# EncoderPCB_V3.net
KiCad netlist of a schematic drawn in EAGLE
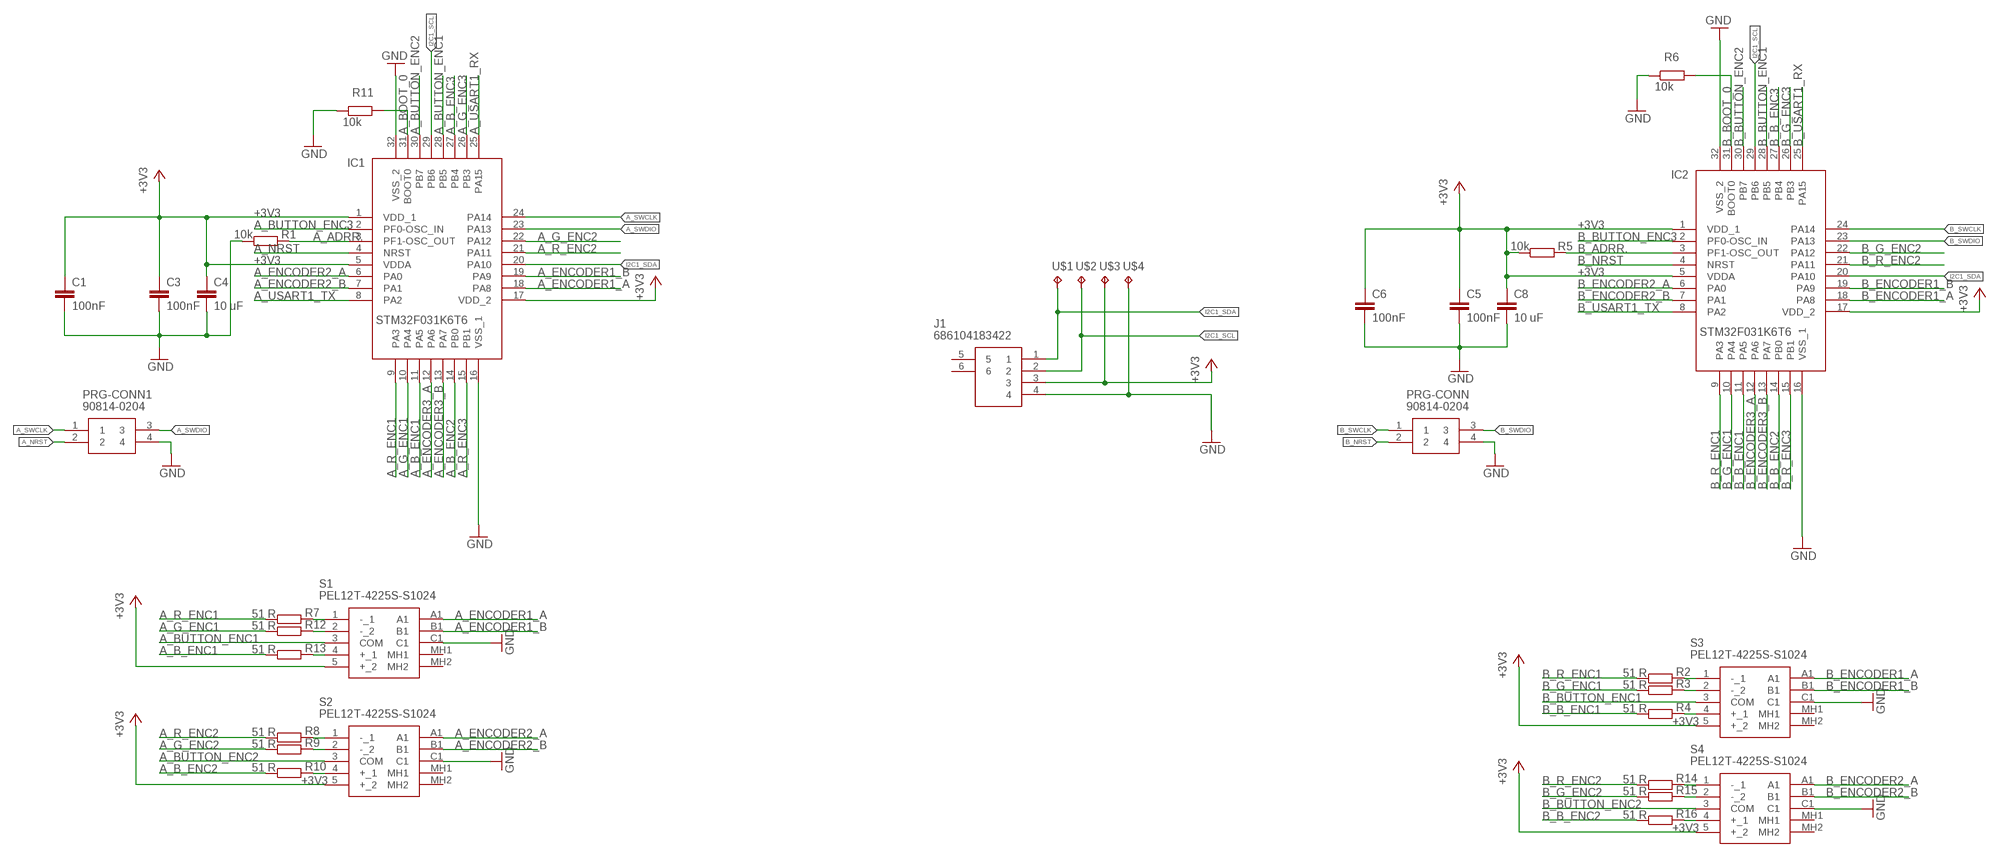
[diagram p0: schematic, sheet 1]

(export (version "E")
  (design (tool "Eeschema 10.0.6"))
  (components
    (comp (ref "C1")
      (value "100nF")
      (footprint "eagle-import:C0603")
      (libsource (lib "eagle-import") (part "CAPACITOR{dblquote}"))
    )
    (comp (ref "C3")
      (value "100nF")
      (footprint "eagle-import:C0603")
      (libsource (lib "eagle-import") (part "CAPACITOR{dblquote}"))
    )
    (comp (ref "C4")
      (value "10 uF")
      (footprint "eagle-import:C1206")
      (libsource (lib "eagle-import") (part "CAPACITOR_1206"))
    )
    (comp (ref "C5")
      (value "100nF")
      (footprint "eagle-import:C0603")
      (libsource (lib "eagle-import") (part "CAPACITOR{dblquote}"))
    )
    (comp (ref "C6")
      (value "100nF")
      (footprint "eagle-import:C0603")
      (libsource (lib "eagle-import") (part "CAPACITOR{dblquote}"))
    )
    (comp (ref "C8")
      (value "10 uF")
      (footprint "eagle-import:C1206")
      (libsource (lib "eagle-import") (part "CAPACITOR_1206"))
    )
    (comp (ref "IC1")
      (value "STM32F031K6T6")
      (footprint "eagle-import:QFP80P900X900X160-32N")
      (fields (field (name "MOUSER_PART_NUMBER") "511-STM32F031K6T6"))
      (libsource (lib "eagle-import") (part "STM32F031K6T6"))
    )
    (comp (ref "IC2")
      (value "STM32F031K6T6")
      (footprint "eagle-import:QFP80P900X900X160-32N")
      (fields (field (name "MOUSER_PART_NUMBER") "511-STM32F031K6T6"))
      (libsource (lib "eagle-import") (part "STM32F031K6T6"))
    )
    (comp (ref "J1")
      (value "686104183422")
      (footprint "eagle-import:686104183422")
      (fields (field (name "MOUSER_PART_NUMBER") "710-686104183422"))
      (libsource (lib "eagle-import") (part "686104183422"))
    )
    (comp (ref "PRG-CONN")
      (value "90814-0204")
      (footprint "eagle-import:MOLEX_90814-0204")
      (fields (field (name "MOUSER_PART_NUMBER") "538-90814-0204"))
      (libsource (lib "eagle-import") (part "90814-0204"))
    )
    (comp (ref "PRG-CONN1")
      (value "90814-0204")
      (footprint "eagle-import:MOLEX_90814-0204")
      (fields (field (name "MOUSER_PART_NUMBER") "538-90814-0204"))
      (libsource (lib "eagle-import") (part "90814-0204"))
    )
    (comp (ref "R1")
      (value "10k")
      (footprint "eagle-import:R0603")
      (libsource (lib "eagle-import") (part "RESISTOR_0603"))
    )
    (comp (ref "R2")
      (value "51 R")
      (footprint "eagle-import:R0603")
      (libsource (lib "eagle-import") (part "RESISTOR_0603"))
    )
    (comp (ref "R3")
      (value "51 R")
      (footprint "eagle-import:R0603")
      (libsource (lib "eagle-import") (part "RESISTOR_0603"))
    )
    (comp (ref "R4")
      (value "51 R")
      (footprint "eagle-import:R0603")
      (libsource (lib "eagle-import") (part "RESISTOR_0603"))
    )
    (comp (ref "R5")
      (value "10k")
      (footprint "eagle-import:R0603")
      (libsource (lib "eagle-import") (part "RESISTOR_0603"))
    )
    (comp (ref "R6")
      (value "10k")
      (footprint "eagle-import:R0603")
      (libsource (lib "eagle-import") (part "RESISTOR_0603"))
    )
    (comp (ref "R7")
      (value "51 R")
      (footprint "eagle-import:R0603")
      (libsource (lib "eagle-import") (part "RESISTOR_0603"))
    )
    (comp (ref "R8")
      (value "51 R")
      (footprint "eagle-import:R0603")
      (libsource (lib "eagle-import") (part "RESISTOR_0603"))
    )
    (comp (ref "R9")
      (value "51 R")
      (footprint "eagle-import:R0603")
      (libsource (lib "eagle-import") (part "RESISTOR_0603"))
    )
    (comp (ref "R10")
      (value "51 R")
      (footprint "eagle-import:R0603")
      (libsource (lib "eagle-import") (part "RESISTOR_0603"))
    )
    (comp (ref "R11")
      (value "10k")
      (footprint "eagle-import:R0603")
      (libsource (lib "eagle-import") (part "RESISTOR_0603"))
    )
    (comp (ref "R12")
      (value "51 R")
      (footprint "eagle-import:R0603")
      (libsource (lib "eagle-import") (part "RESISTOR_0603"))
    )
    (comp (ref "R13")
      (value "51 R")
      (footprint "eagle-import:R0603")
      (libsource (lib "eagle-import") (part "RESISTOR_0603"))
    )
    (comp (ref "R14")
      (value "51 R")
      (footprint "eagle-import:R0603")
      (libsource (lib "eagle-import") (part "RESISTOR_0603"))
    )
    (comp (ref "R15")
      (value "51 R")
      (footprint "eagle-import:R0603")
      (libsource (lib "eagle-import") (part "RESISTOR_0603"))
    )
    (comp (ref "R16")
      (value "51 R")
      (footprint "eagle-import:R0603")
      (libsource (lib "eagle-import") (part "RESISTOR_0603"))
    )
    (comp (ref "S1")
      (value "PEL12T-4225S-S1024")
      (footprint "eagle-import:PEL12T4225SS1024")
      (fields (field (name "MOUSER_PART_NUMBER") "652-PEL12T4225SS1024"))
      (libsource (lib "eagle-import") (part "PEL12T-4225S-S1024"))
    )
    (comp (ref "S2")
      (value "PEL12T-4225S-S1024")
      (footprint "eagle-import:PEL12T4225SS1024")
      (fields (field (name "MOUSER_PART_NUMBER") "652-PEL12T4225SS1024"))
      (libsource (lib "eagle-import") (part "PEL12T-4225S-S1024"))
    )
    (comp (ref "S3")
      (value "PEL12T-4225S-S1024")
      (footprint "eagle-import:PEL12T4225SS1024")
      (fields (field (name "MOUSER_PART_NUMBER") "652-PEL12T4225SS1024"))
      (libsource (lib "eagle-import") (part "PEL12T-4225S-S1024"))
    )
    (comp (ref "S4")
      (value "PEL12T-4225S-S1024")
      (footprint "eagle-import:PEL12T4225SS1024")
      (fields (field (name "MOUSER_PART_NUMBER") "652-PEL12T4225SS1024"))
      (libsource (lib "eagle-import") (part "PEL12T-4225S-S1024"))
    )
    (comp (ref "U$1")
      (value "TP")
      (footprint "eagle-import:OVAL_PAD")
      (libsource (lib "eagle-import") (part "TP"))
    )
    (comp (ref "U$2")
      (value "TP")
      (footprint "eagle-import:OVAL_PAD")
      (libsource (lib "eagle-import") (part "TP"))
    )
    (comp (ref "U$3")
      (value "TP")
      (footprint "eagle-import:OVAL_PAD")
      (libsource (lib "eagle-import") (part "TP"))
    )
    (comp (ref "U$4")
      (value "TP")
      (footprint "eagle-import:OVAL_PAD")
      (libsource (lib "eagle-import") (part "TP"))
    )
  )
  (nets
    (net (code "1") (name "+3V3") (class "Default")
      (node (ref "C1") (pin "1") (pinfunction "1_1") (pintype "passive"))
      (node (ref "C3") (pin "1") (pinfunction "1_1") (pintype "passive"))
      (node (ref "C4") (pin "1") (pinfunction "1_1") (pintype "passive"))
      (node (ref "C5") (pin "1") (pinfunction "1_1") (pintype "passive"))
      (node (ref "C6") (pin "1") (pinfunction "1_1") (pintype "passive"))
      (node (ref "C8") (pin "1") (pinfunction "1_1") (pintype "passive"))
      (node (ref "IC1") (pin "1") (pinfunction "VDD_1_1") (pintype "bidirectional"))
      (node (ref "IC1") (pin "17") (pinfunction "VDD_2_17") (pintype "bidirectional"))
      (node (ref "IC1") (pin "5") (pinfunction "VDDA_5") (pintype "bidirectional"))
      (node (ref "IC2") (pin "1") (pinfunction "VDD_1_1") (pintype "bidirectional"))
      (node (ref "IC2") (pin "17") (pinfunction "VDD_2_17") (pintype "bidirectional"))
      (node (ref "IC2") (pin "5") (pinfunction "VDDA_5") (pintype "bidirectional"))
      (node (ref "J1") (pin "3") (pinfunction "3_3") (pintype "bidirectional"))
      (node (ref "R5") (pin "1") (pinfunction "1_1") (pintype "passive"))
      (node (ref "S1") (pin "5") (pinfunction "+_2_5") (pintype "bidirectional"))
      (node (ref "S2") (pin "5") (pinfunction "+_2_5") (pintype "bidirectional"))
      (node (ref "S3") (pin "5") (pinfunction "+_2_5") (pintype "bidirectional"))
      (node (ref "S4") (pin "5") (pinfunction "+_2_5") (pintype "bidirectional"))
      (node (ref "U$3") (pin "P$1") (pinfunction "TP_P$1") (pintype "input"))
    )
    (net (code "2") (name "/A_ADRR.") (class "Default")
      (node (ref "IC1") (pin "3") (pinfunction "PF1-OSC_OUT_3") (pintype "bidirectional"))
      (node (ref "R1") (pin "2") (pinfunction "2_2") (pintype "passive"))
    )
    (net (code "3") (name "/A_BOOT_0") (class "Default")
      (node (ref "IC1") (pin "31") (pinfunction "BOOT0_31") (pintype "bidirectional"))
      (node (ref "R11") (pin "2") (pinfunction "2_2") (pintype "passive"))
    )
    (net (code "4") (name "/A_BUTTON_ENC1") (class "Default")
      (node (ref "IC1") (pin "28") (pinfunction "PB5_28") (pintype "bidirectional"))
      (node (ref "S1") (pin "3") (pinfunction "COM_3") (pintype "bidirectional"))
    )
    (net (code "5") (name "/A_BUTTON_ENC2") (class "Default")
      (node (ref "IC1") (pin "30") (pinfunction "PB7_30") (pintype "bidirectional"))
      (node (ref "S2") (pin "3") (pinfunction "COM_3") (pintype "bidirectional"))
    )
    (net (code "6") (name "/A_BUTTON_ENC3") (class "Default")
      (node (ref "IC1") (pin "2") (pinfunction "PF0-OSC_IN_2") (pintype "bidirectional"))
    )
    (net (code "7") (name "/A_B_ENC1") (class "Default")
      (node (ref "IC1") (pin "11") (pinfunction "PA5_11") (pintype "bidirectional"))
      (node (ref "R13") (pin "1") (pinfunction "1_1") (pintype "passive"))
    )
    (net (code "8") (name "/A_B_ENC2") (class "Default")
      (node (ref "IC1") (pin "14") (pinfunction "PB0_14") (pintype "bidirectional"))
      (node (ref "R10") (pin "1") (pinfunction "1_1") (pintype "passive"))
    )
    (net (code "9") (name "/A_B_ENC3") (class "Default")
      (node (ref "IC1") (pin "27") (pinfunction "PB4_27") (pintype "bidirectional"))
    )
    (net (code "10") (name "/A_ENCODER1_A") (class "Default")
      (node (ref "IC1") (pin "18") (pinfunction "PA8_18") (pintype "bidirectional"))
      (node (ref "S1") (pin "A1") (pinfunction "A1_A1") (pintype "bidirectional"))
    )
    (net (code "11") (name "/A_ENCODER1_B") (class "Default")
      (node (ref "IC1") (pin "19") (pinfunction "PA9_19") (pintype "bidirectional"))
      (node (ref "S1") (pin "B1") (pinfunction "B1_B1") (pintype "bidirectional"))
    )
    (net (code "12") (name "/A_ENCODER2_A") (class "Default")
      (node (ref "IC1") (pin "6") (pinfunction "PA0_6") (pintype "bidirectional"))
      (node (ref "S2") (pin "A1") (pinfunction "A1_A1") (pintype "bidirectional"))
    )
    (net (code "13") (name "/A_ENCODER2_B") (class "Default")
      (node (ref "IC1") (pin "7") (pinfunction "PA1_7") (pintype "bidirectional"))
      (node (ref "S2") (pin "B1") (pinfunction "B1_B1") (pintype "bidirectional"))
    )
    (net (code "14") (name "/A_ENCODER3_A") (class "Default")
      (node (ref "IC1") (pin "12") (pinfunction "PA6_12") (pintype "bidirectional"))
    )
    (net (code "15") (name "/A_ENCODER3_B") (class "Default")
      (node (ref "IC1") (pin "13") (pinfunction "PA7_13") (pintype "bidirectional"))
    )
    (net (code "16") (name "/A_G_ENC1") (class "Default")
      (node (ref "IC1") (pin "10") (pinfunction "PA4_10") (pintype "bidirectional"))
      (node (ref "R12") (pin "1") (pinfunction "1_1") (pintype "passive"))
    )
    (net (code "17") (name "/A_G_ENC2") (class "Default")
      (node (ref "IC1") (pin "22") (pinfunction "PA12_22") (pintype "bidirectional"))
      (node (ref "R9") (pin "1") (pinfunction "1_1") (pintype "passive"))
    )
    (net (code "18") (name "/A_G_ENC3") (class "Default")
      (node (ref "IC1") (pin "26") (pinfunction "PB3_26") (pintype "bidirectional"))
    )
    (net (code "19") (name "/A_R_ENC1") (class "Default")
      (node (ref "IC1") (pin "9") (pinfunction "PA3_9") (pintype "bidirectional"))
      (node (ref "R7") (pin "1") (pinfunction "1_1") (pintype "passive"))
    )
    (net (code "20") (name "/A_R_ENC2") (class "Default")
      (node (ref "IC1") (pin "21") (pinfunction "PA11_21") (pintype "bidirectional"))
      (node (ref "R8") (pin "1") (pinfunction "1_1") (pintype "passive"))
    )
    (net (code "21") (name "/A_R_ENC3") (class "Default")
      (node (ref "IC1") (pin "15") (pinfunction "PB1_15") (pintype "bidirectional"))
    )
    (net (code "22") (name "/A_USART1_RX") (class "Default")
      (node (ref "IC1") (pin "25") (pinfunction "PA15_25") (pintype "bidirectional"))
    )
    (net (code "23") (name "/A_USART1_TX") (class "Default")
      (node (ref "IC1") (pin "8") (pinfunction "PA2_8") (pintype "bidirectional"))
    )
    (net (code "24") (name "/B_ADRR.") (class "Default")
      (node (ref "IC2") (pin "3") (pinfunction "PF1-OSC_OUT_3") (pintype "bidirectional"))
      (node (ref "R5") (pin "2") (pinfunction "2_2") (pintype "passive"))
    )
    (net (code "25") (name "/B_BOOT_0") (class "Default")
      (node (ref "IC2") (pin "31") (pinfunction "BOOT0_31") (pintype "bidirectional"))
      (node (ref "R6") (pin "2") (pinfunction "2_2") (pintype "passive"))
    )
    (net (code "26") (name "/B_BUTTON_ENC1") (class "Default")
      (node (ref "IC2") (pin "28") (pinfunction "PB5_28") (pintype "bidirectional"))
      (node (ref "S3") (pin "3") (pinfunction "COM_3") (pintype "bidirectional"))
    )
    (net (code "27") (name "/B_BUTTON_ENC2") (class "Default")
      (node (ref "IC2") (pin "30") (pinfunction "PB7_30") (pintype "bidirectional"))
      (node (ref "S4") (pin "3") (pinfunction "COM_3") (pintype "bidirectional"))
    )
    (net (code "28") (name "/B_BUTTON_ENC3") (class "Default")
      (node (ref "IC2") (pin "2") (pinfunction "PF0-OSC_IN_2") (pintype "bidirectional"))
    )
    (net (code "29") (name "/B_B_ENC1") (class "Default")
      (node (ref "IC2") (pin "11") (pinfunction "PA5_11") (pintype "bidirectional"))
      (node (ref "R4") (pin "1") (pinfunction "1_1") (pintype "passive"))
    )
    (net (code "30") (name "/B_B_ENC2") (class "Default")
      (node (ref "IC2") (pin "14") (pinfunction "PB0_14") (pintype "bidirectional"))
      (node (ref "R16") (pin "1") (pinfunction "1_1") (pintype "passive"))
    )
    (net (code "31") (name "/B_B_ENC3") (class "Default")
      (node (ref "IC2") (pin "27") (pinfunction "PB4_27") (pintype "bidirectional"))
    )
    (net (code "32") (name "/B_ENCODER1_A") (class "Default")
      (node (ref "IC2") (pin "18") (pinfunction "PA8_18") (pintype "bidirectional"))
      (node (ref "S3") (pin "A1") (pinfunction "A1_A1") (pintype "bidirectional"))
    )
    (net (code "33") (name "/B_ENCODER1_B") (class "Default")
      (node (ref "IC2") (pin "19") (pinfunction "PA9_19") (pintype "bidirectional"))
      (node (ref "S3") (pin "B1") (pinfunction "B1_B1") (pintype "bidirectional"))
    )
    (net (code "34") (name "/B_ENCODER2_A") (class "Default")
      (node (ref "IC2") (pin "6") (pinfunction "PA0_6") (pintype "bidirectional"))
      (node (ref "S4") (pin "A1") (pinfunction "A1_A1") (pintype "bidirectional"))
    )
    (net (code "35") (name "/B_ENCODER2_B") (class "Default")
      (node (ref "IC2") (pin "7") (pinfunction "PA1_7") (pintype "bidirectional"))
      (node (ref "S4") (pin "B1") (pinfunction "B1_B1") (pintype "bidirectional"))
    )
    (net (code "36") (name "/B_ENCODER3_A") (class "Default")
      (node (ref "IC2") (pin "12") (pinfunction "PA6_12") (pintype "bidirectional"))
    )
    (net (code "37") (name "/B_ENCODER3_B") (class "Default")
      (node (ref "IC2") (pin "13") (pinfunction "PA7_13") (pintype "bidirectional"))
    )
    (net (code "38") (name "/B_G_ENC1") (class "Default")
      (node (ref "IC2") (pin "10") (pinfunction "PA4_10") (pintype "bidirectional"))
      (node (ref "R3") (pin "1") (pinfunction "1_1") (pintype "passive"))
    )
    (net (code "39") (name "/B_G_ENC2") (class "Default")
      (node (ref "IC2") (pin "22") (pinfunction "PA12_22") (pintype "bidirectional"))
      (node (ref "R15") (pin "1") (pinfunction "1_1") (pintype "passive"))
    )
    (net (code "40") (name "/B_G_ENC3") (class "Default")
      (node (ref "IC2") (pin "26") (pinfunction "PB3_26") (pintype "bidirectional"))
    )
    (net (code "41") (name "/B_R_ENC1") (class "Default")
      (node (ref "IC2") (pin "9") (pinfunction "PA3_9") (pintype "bidirectional"))
      (node (ref "R2") (pin "1") (pinfunction "1_1") (pintype "passive"))
    )
    (net (code "42") (name "/B_R_ENC2") (class "Default")
      (node (ref "IC2") (pin "21") (pinfunction "PA11_21") (pintype "bidirectional"))
      (node (ref "R14") (pin "1") (pinfunction "1_1") (pintype "passive"))
    )
    (net (code "43") (name "/B_R_ENC3") (class "Default")
      (node (ref "IC2") (pin "15") (pinfunction "PB1_15") (pintype "bidirectional"))
    )
    (net (code "44") (name "/B_USART1_RX") (class "Default")
      (node (ref "IC2") (pin "25") (pinfunction "PA15_25") (pintype "bidirectional"))
    )
    (net (code "45") (name "/B_USART1_TX") (class "Default")
      (node (ref "IC2") (pin "8") (pinfunction "PA2_8") (pintype "bidirectional"))
    )
    (net (code "46") (name "A_NRST") (class "Default")
      (node (ref "IC1") (pin "4") (pinfunction "NRST_4") (pintype "bidirectional"))
      (node (ref "PRG-CONN1") (pin "2") (pinfunction "2_2") (pintype "bidirectional"))
    )
    (net (code "47") (name "A_SWCLK") (class "Default")
      (node (ref "IC1") (pin "24") (pinfunction "PA14_24") (pintype "bidirectional"))
      (node (ref "PRG-CONN1") (pin "1") (pinfunction "1_1") (pintype "bidirectional"))
    )
    (net (code "48") (name "A_SWDIO") (class "Default")
      (node (ref "IC1") (pin "23") (pinfunction "PA13_23") (pintype "bidirectional"))
      (node (ref "PRG-CONN1") (pin "3") (pinfunction "3_3") (pintype "bidirectional"))
    )
    (net (code "49") (name "B_NRST") (class "Default")
      (node (ref "IC2") (pin "4") (pinfunction "NRST_4") (pintype "bidirectional"))
      (node (ref "PRG-CONN") (pin "2") (pinfunction "2_2") (pintype "bidirectional"))
    )
    (net (code "50") (name "B_SWCLK") (class "Default")
      (node (ref "IC2") (pin "24") (pinfunction "PA14_24") (pintype "bidirectional"))
      (node (ref "PRG-CONN") (pin "1") (pinfunction "1_1") (pintype "bidirectional"))
    )
    (net (code "51") (name "B_SWDIO") (class "Default")
      (node (ref "IC2") (pin "23") (pinfunction "PA13_23") (pintype "bidirectional"))
      (node (ref "PRG-CONN") (pin "3") (pinfunction "3_3") (pintype "bidirectional"))
    )
    (net (code "52") (name "GND") (class "Default")
      (node (ref "C1") (pin "2") (pinfunction "2_2") (pintype "passive"))
      (node (ref "C3") (pin "2") (pinfunction "2_2") (pintype "passive"))
      (node (ref "C4") (pin "2") (pinfunction "2_2") (pintype "passive"))
      (node (ref "C5") (pin "2") (pinfunction "2_2") (pintype "passive"))
      (node (ref "C6") (pin "2") (pinfunction "2_2") (pintype "passive"))
      (node (ref "C8") (pin "2") (pinfunction "2_2") (pintype "passive"))
      (node (ref "IC1") (pin "16") (pinfunction "VSS_1_16") (pintype "bidirectional"))
      (node (ref "IC1") (pin "32") (pinfunction "VSS_2_32") (pintype "bidirectional"))
      (node (ref "IC2") (pin "16") (pinfunction "VSS_1_16") (pintype "bidirectional"))
      (node (ref "IC2") (pin "32") (pinfunction "VSS_2_32") (pintype "bidirectional"))
      (node (ref "J1") (pin "4") (pinfunction "4_4") (pintype "bidirectional"))
      (node (ref "PRG-CONN") (pin "4") (pinfunction "4_4") (pintype "bidirectional"))
      (node (ref "PRG-CONN1") (pin "4") (pinfunction "4_4") (pintype "bidirectional"))
      (node (ref "R1") (pin "1") (pinfunction "1_1") (pintype "passive"))
      (node (ref "R11") (pin "1") (pinfunction "1_1") (pintype "passive"))
      (node (ref "R6") (pin "1") (pinfunction "1_1") (pintype "passive"))
      (node (ref "S1") (pin "C1") (pinfunction "C1_C1") (pintype "bidirectional"))
      (node (ref "S2") (pin "C1") (pinfunction "C1_C1") (pintype "bidirectional"))
      (node (ref "S3") (pin "C1") (pinfunction "C1_C1") (pintype "bidirectional"))
      (node (ref "S4") (pin "C1") (pinfunction "C1_C1") (pintype "bidirectional"))
      (node (ref "U$4") (pin "P$1") (pinfunction "TP_P$1") (pintype "input"))
    )
    (net (code "53") (name "I2C1_SCL") (class "Default")
      (node (ref "IC1") (pin "29") (pinfunction "PB6_29") (pintype "bidirectional"))
      (node (ref "IC2") (pin "29") (pinfunction "PB6_29") (pintype "bidirectional"))
      (node (ref "J1") (pin "2") (pinfunction "2_2") (pintype "bidirectional"))
      (node (ref "U$2") (pin "P$1") (pinfunction "TP_P$1") (pintype "input"))
    )
    (net (code "54") (name "I2C1_SDA") (class "Default")
      (node (ref "IC1") (pin "20") (pinfunction "PA10_20") (pintype "bidirectional"))
      (node (ref "IC2") (pin "20") (pinfunction "PA10_20") (pintype "bidirectional"))
      (node (ref "J1") (pin "1") (pinfunction "1_1") (pintype "bidirectional"))
      (node (ref "U$1") (pin "P$1") (pinfunction "TP_P$1") (pintype "input"))
    )
    (net (code "55") (name "Net-(S1-+_1)") (class "Default")
      (node (ref "R13") (pin "2") (pinfunction "2_2") (pintype "passive"))
      (node (ref "S1") (pin "4") (pinfunction "+_1_4") (pintype "bidirectional"))
    )
    (net (code "56") (name "Net-(S1--_1)") (class "Default")
      (node (ref "R7") (pin "2") (pinfunction "2_2") (pintype "passive"))
      (node (ref "S1") (pin "1") (pinfunction "-_1_1") (pintype "bidirectional"))
    )
    (net (code "57") (name "Net-(S1--_2)") (class "Default")
      (node (ref "R12") (pin "2") (pinfunction "2_2") (pintype "passive"))
      (node (ref "S1") (pin "2") (pinfunction "-_2_2") (pintype "bidirectional"))
    )
    (net (code "58") (name "Net-(S2-+_1)") (class "Default")
      (node (ref "R10") (pin "2") (pinfunction "2_2") (pintype "passive"))
      (node (ref "S2") (pin "4") (pinfunction "+_1_4") (pintype "bidirectional"))
    )
    (net (code "59") (name "Net-(S2--_1)") (class "Default")
      (node (ref "R8") (pin "2") (pinfunction "2_2") (pintype "passive"))
      (node (ref "S2") (pin "1") (pinfunction "-_1_1") (pintype "bidirectional"))
    )
    (net (code "60") (name "Net-(S2--_2)") (class "Default")
      (node (ref "R9") (pin "2") (pinfunction "2_2") (pintype "passive"))
      (node (ref "S2") (pin "2") (pinfunction "-_2_2") (pintype "bidirectional"))
    )
    (net (code "61") (name "Net-(S3-+_1)") (class "Default")
      (node (ref "R4") (pin "2") (pinfunction "2_2") (pintype "passive"))
      (node (ref "S3") (pin "4") (pinfunction "+_1_4") (pintype "bidirectional"))
    )
    (net (code "62") (name "Net-(S3--_1)") (class "Default")
      (node (ref "R2") (pin "2") (pinfunction "2_2") (pintype "passive"))
      (node (ref "S3") (pin "1") (pinfunction "-_1_1") (pintype "bidirectional"))
    )
    (net (code "63") (name "Net-(S3--_2)") (class "Default")
      (node (ref "R3") (pin "2") (pinfunction "2_2") (pintype "passive"))
      (node (ref "S3") (pin "2") (pinfunction "-_2_2") (pintype "bidirectional"))
    )
    (net (code "64") (name "Net-(S4-+_1)") (class "Default")
      (node (ref "R16") (pin "2") (pinfunction "2_2") (pintype "passive"))
      (node (ref "S4") (pin "4") (pinfunction "+_1_4") (pintype "bidirectional"))
    )
    (net (code "65") (name "Net-(S4--_1)") (class "Default")
      (node (ref "R14") (pin "2") (pinfunction "2_2") (pintype "passive"))
      (node (ref "S4") (pin "1") (pinfunction "-_1_1") (pintype "bidirectional"))
    )
    (net (code "66") (name "Net-(S4--_2)") (class "Default")
      (node (ref "R15") (pin "2") (pinfunction "2_2") (pintype "passive"))
      (node (ref "S4") (pin "2") (pinfunction "-_2_2") (pintype "bidirectional"))
    )
    (net (code "67") (name "unconnected-(J1-Pad5)") (class "Default")
      (node (ref "J1") (pin "5") (pinfunction "5_5") (pintype "bidirectional"))
    )
    (net (code "68") (name "unconnected-(J1-Pad6)") (class "Default")
      (node (ref "J1") (pin "6") (pinfunction "6_6") (pintype "bidirectional"))
    )
    (net (code "69") (name "unconnected-(S1-PadMH1)") (class "Default")
      (node (ref "S1") (pin "MH1") (pinfunction "MH1_MH1") (pintype "bidirectional"))
    )
    (net (code "70") (name "unconnected-(S1-PadMH2)") (class "Default")
      (node (ref "S1") (pin "MH2") (pinfunction "MH2_MH2") (pintype "bidirectional"))
    )
    (net (code "71") (name "unconnected-(S2-PadMH1)") (class "Default")
      (node (ref "S2") (pin "MH1") (pinfunction "MH1_MH1") (pintype "bidirectional"))
    )
    (net (code "72") (name "unconnected-(S2-PadMH2)") (class "Default")
      (node (ref "S2") (pin "MH2") (pinfunction "MH2_MH2") (pintype "bidirectional"))
    )
    (net (code "73") (name "unconnected-(S3-PadMH1)") (class "Default")
      (node (ref "S3") (pin "MH1") (pinfunction "MH1_MH1") (pintype "bidirectional"))
    )
    (net (code "74") (name "unconnected-(S3-PadMH2)") (class "Default")
      (node (ref "S3") (pin "MH2") (pinfunction "MH2_MH2") (pintype "bidirectional"))
    )
    (net (code "75") (name "unconnected-(S4-PadMH1)") (class "Default")
      (node (ref "S4") (pin "MH1") (pinfunction "MH1_MH1") (pintype "bidirectional"))
    )
    (net (code "76") (name "unconnected-(S4-PadMH2)") (class "Default")
      (node (ref "S4") (pin "MH2") (pinfunction "MH2_MH2") (pintype "bidirectional"))
    )
  )
)
